# relay_module.net
KiCad netlist of a schematic drawn in EAGLE
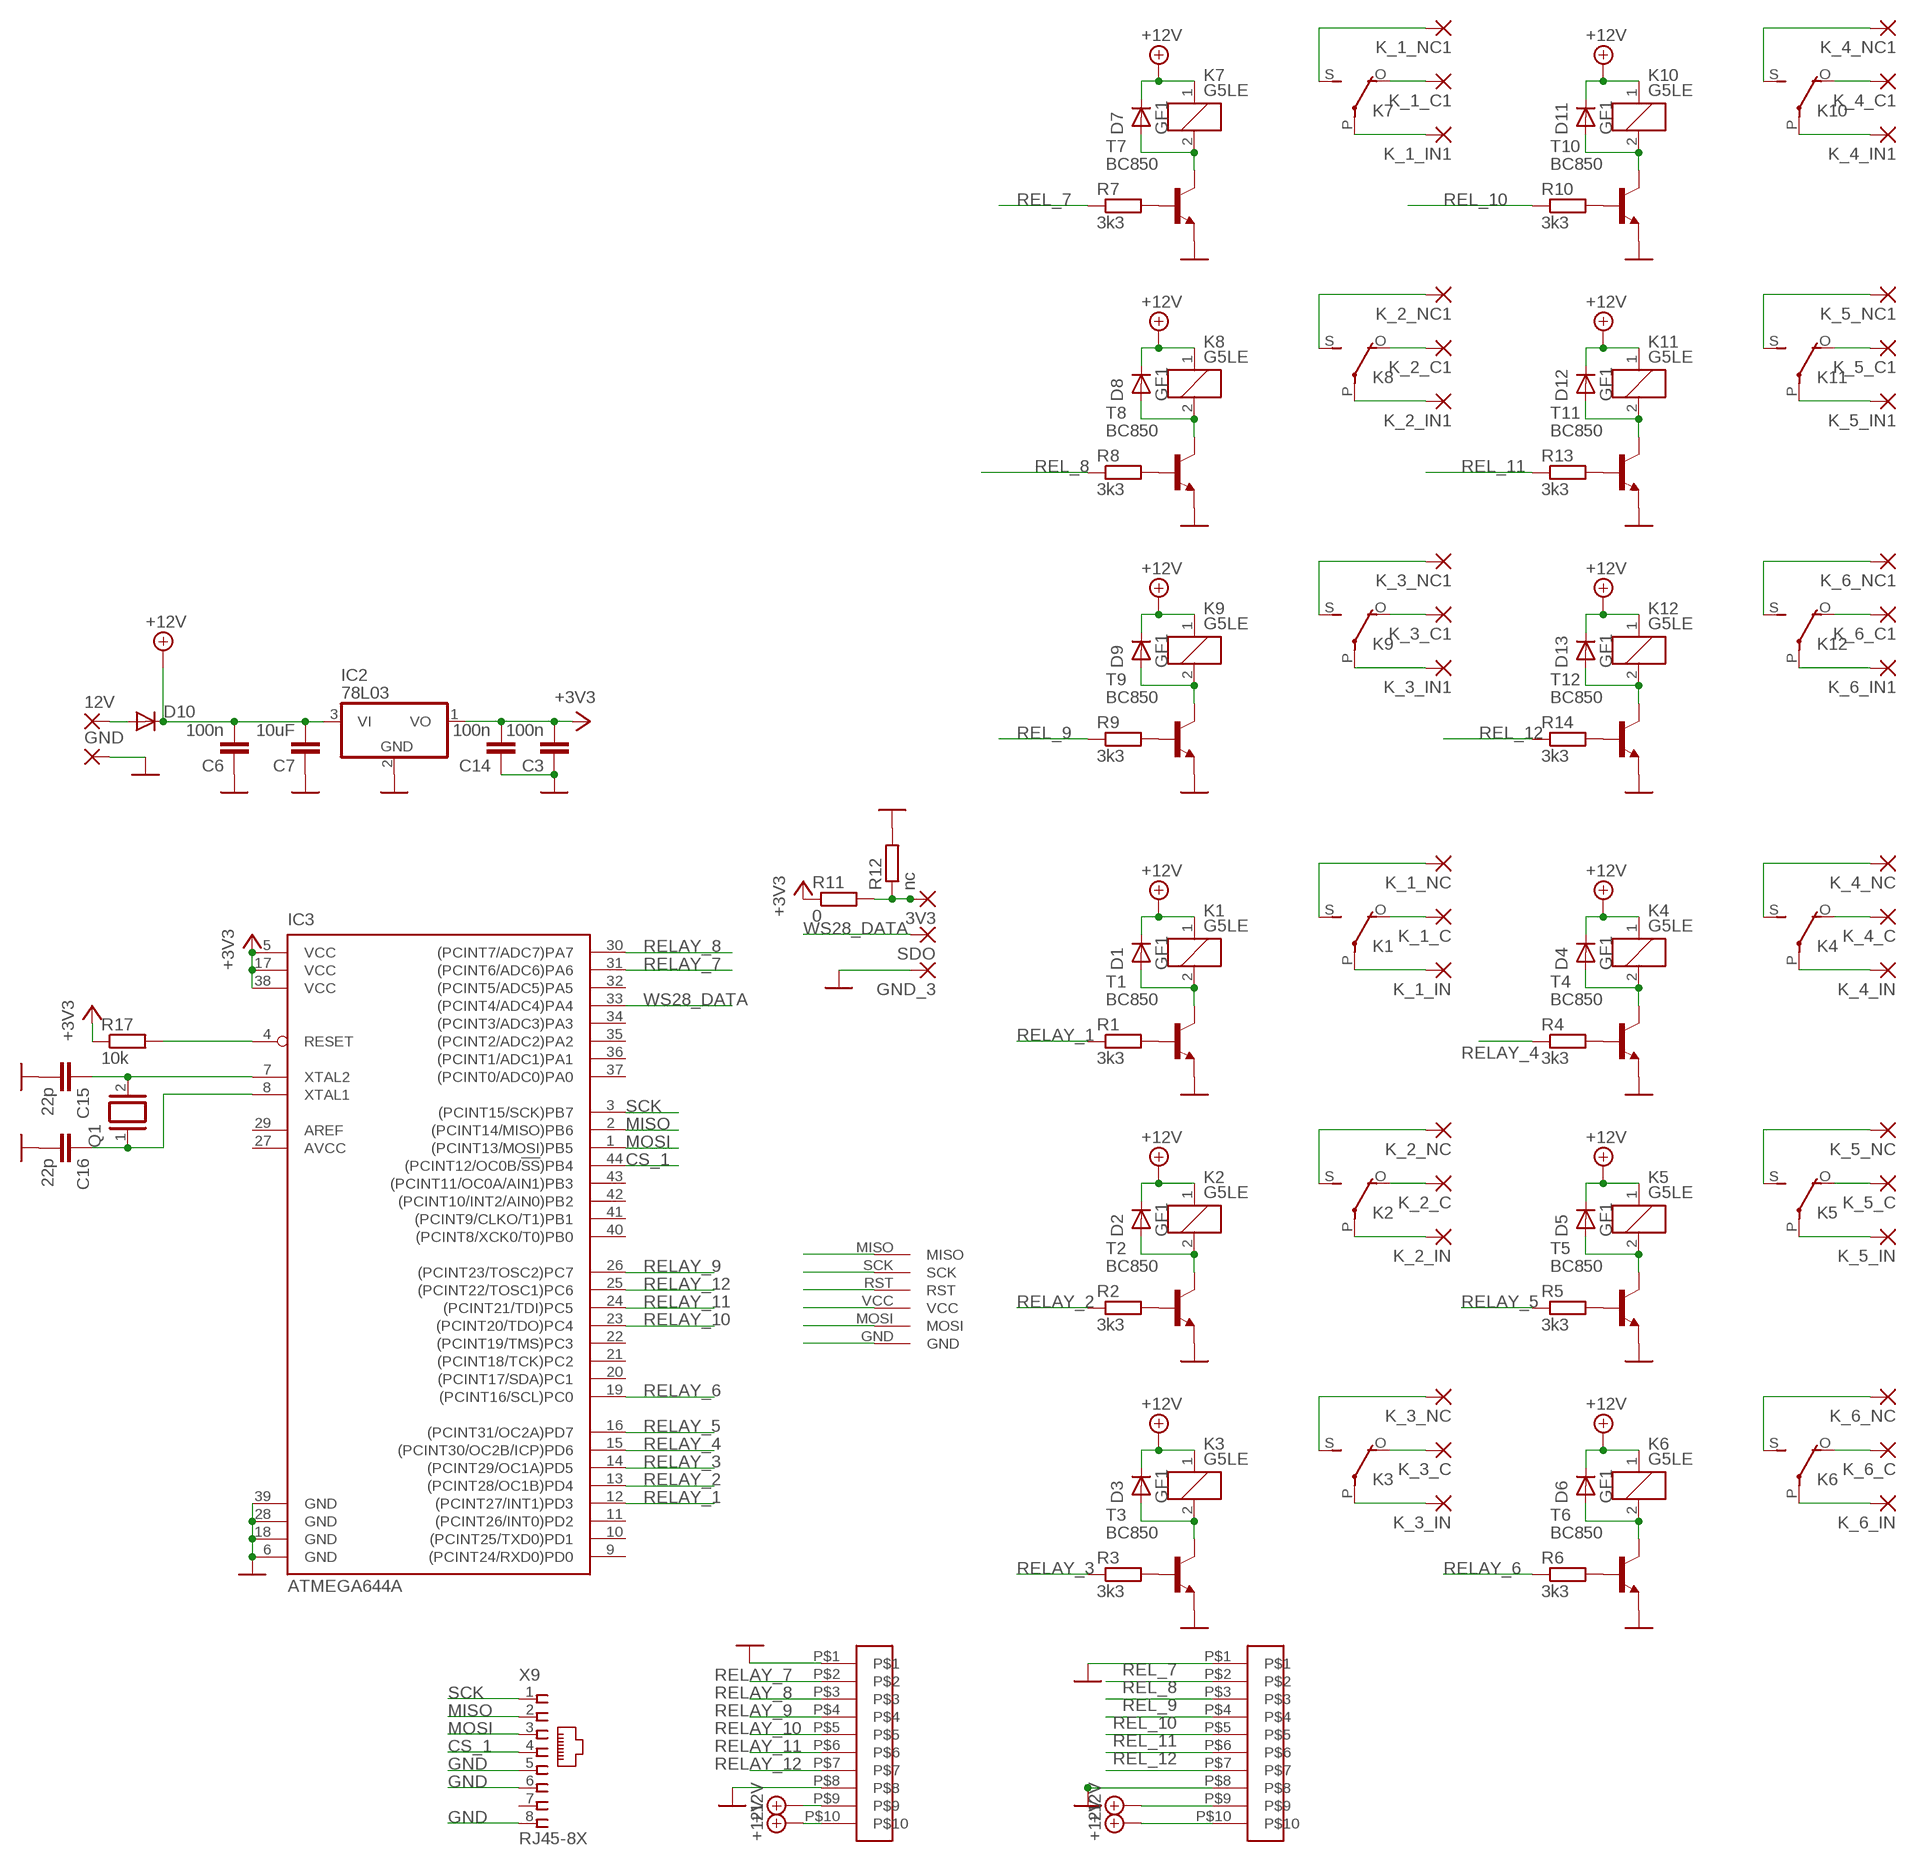
[diagram p0: schematic, sheet 1]

(export (version "E")
  (design (tool "Eeschema 10.0.6"))
  (components
    (comp (ref "3V3")
      (value "2,15/1,0")
      (footprint "eagle-import:2,15_1,0")
      (libsource (lib "eagle-import") (part "2,15/1,0"))
    )
    (comp (ref "12V")
      (value "2,54/0,8")
      (footprint "eagle-import:2,54_0,8")
      (libsource (lib "eagle-import") (part "2,54/0,8"))
    )
    (comp (ref "C3")
      (value "100n")
      (footprint "eagle-import:C1206")
      (libsource (lib "eagle-import") (part "C-EUC1206"))
    )
    (comp (ref "C6")
      (value "100n")
      (footprint "eagle-import:C1206")
      (libsource (lib "eagle-import") (part "C-EUC1206"))
    )
    (comp (ref "C7")
      (value "10uF")
      (footprint "eagle-import:C1206")
      (libsource (lib "eagle-import") (part "C-EUC1206"))
    )
    (comp (ref "C14")
      (value "100n")
      (footprint "eagle-import:C1206")
      (libsource (lib "eagle-import") (part "C-EUC1206"))
    )
    (comp (ref "C15")
      (value "22p")
      (footprint "eagle-import:C1206")
      (libsource (lib "eagle-import") (part "C-EUC1206"))
    )
    (comp (ref "C16")
      (value "22p")
      (footprint "eagle-import:C1206")
      (libsource (lib "eagle-import") (part "C-EUC1206"))
    )
    (comp (ref "D1")
      (value "GF1")
      (footprint "eagle-import:SMA-DO214AC")
      (libsource (lib "eagle-import") (part "GF1"))
    )
    (comp (ref "D2")
      (value "GF1")
      (footprint "eagle-import:SMA-DO214AC")
      (libsource (lib "eagle-import") (part "GF1"))
    )
    (comp (ref "D3")
      (value "GF1")
      (footprint "eagle-import:SMA-DO214AC")
      (libsource (lib "eagle-import") (part "GF1"))
    )
    (comp (ref "D4")
      (value "GF1")
      (footprint "eagle-import:SMA-DO214AC")
      (libsource (lib "eagle-import") (part "GF1"))
    )
    (comp (ref "D5")
      (value "GF1")
      (footprint "eagle-import:SMA-DO214AC")
      (libsource (lib "eagle-import") (part "GF1"))
    )
    (comp (ref "D6")
      (value "GF1")
      (footprint "eagle-import:SMA-DO214AC")
      (libsource (lib "eagle-import") (part "GF1"))
    )
    (comp (ref "D7")
      (value "GF1")
      (footprint "eagle-import:SMA-DO214AC")
      (libsource (lib "eagle-import") (part "GF1"))
    )
    (comp (ref "D8")
      (value "GF1")
      (footprint "eagle-import:SMA-DO214AC")
      (libsource (lib "eagle-import") (part "GF1"))
    )
    (comp (ref "D9")
      (value "GF1")
      (footprint "eagle-import:SMA-DO214AC")
      (libsource (lib "eagle-import") (part "GF1"))
    )
    (comp (ref "D10")
      (value "1N4148DO35-10")
      (footprint "eagle-import:DO35-10")
      (libsource (lib "eagle-import") (part "1N4148DO35-10"))
    )
    (comp (ref "D11")
      (value "GF1")
      (footprint "eagle-import:SMA-DO214AC")
      (libsource (lib "eagle-import") (part "GF1"))
    )
    (comp (ref "D12")
      (value "GF1")
      (footprint "eagle-import:SMA-DO214AC")
      (libsource (lib "eagle-import") (part "GF1"))
    )
    (comp (ref "D13")
      (value "GF1")
      (footprint "eagle-import:SMA-DO214AC")
      (libsource (lib "eagle-import") (part "GF1"))
    )
    (comp (ref "GND")
      (value "2,54/0,8")
      (footprint "eagle-import:2,54_0,8")
      (libsource (lib "eagle-import") (part "2,54/0,8"))
    )
    (comp (ref "GND_3")
      (value "2,15/1,0")
      (footprint "eagle-import:2,15_1,0")
      (libsource (lib "eagle-import") (part "2,15/1,0"))
    )
    (comp (ref "IC2")
      (value "78L03")
      (footprint "eagle-import:TO92")
      (libsource (lib "eagle-import") (part "78ZL05"))
    )
    (comp (ref "IC3")
      (value "ATMEGA644A")
      (footprint "eagle-import:TQFP44")
      (fields (field (name "MPN") "ATMEGA644PV-10AU"))
      (libsource (lib "eagle-import") (part "ATMEGA644A"))
    )
    (comp (ref "K1")
      (value "G5LE")
      (footprint "eagle-import:G5LE")
      (libsource (lib "eagle-import") (part "G5LE"))
    )
    (comp (ref "K2")
      (value "G5LE")
      (footprint "eagle-import:G5LE")
      (libsource (lib "eagle-import") (part "G5LE"))
    )
    (comp (ref "K3")
      (value "G5LE")
      (footprint "eagle-import:G5LE")
      (libsource (lib "eagle-import") (part "G5LE"))
    )
    (comp (ref "K4")
      (value "G5LE")
      (footprint "eagle-import:G5LE")
      (libsource (lib "eagle-import") (part "G5LE"))
    )
    (comp (ref "K5")
      (value "G5LE")
      (footprint "eagle-import:G5LE")
      (libsource (lib "eagle-import") (part "G5LE"))
    )
    (comp (ref "K6")
      (value "G5LE")
      (footprint "eagle-import:G5LE")
      (libsource (lib "eagle-import") (part "G5LE"))
    )
    (comp (ref "K7")
      (value "G5LE")
      (footprint "eagle-import:G5LE")
      (libsource (lib "eagle-import") (part "G5LE"))
    )
    (comp (ref "K8")
      (value "G5LE")
      (footprint "eagle-import:G5LE")
      (libsource (lib "eagle-import") (part "G5LE"))
    )
    (comp (ref "K9")
      (value "G5LE")
      (footprint "eagle-import:G5LE")
      (libsource (lib "eagle-import") (part "G5LE"))
    )
    (comp (ref "K10")
      (value "G5LE")
      (footprint "eagle-import:G5LE")
      (libsource (lib "eagle-import") (part "G5LE"))
    )
    (comp (ref "K11")
      (value "G5LE")
      (footprint "eagle-import:G5LE")
      (libsource (lib "eagle-import") (part "G5LE"))
    )
    (comp (ref "K12")
      (value "G5LE")
      (footprint "eagle-import:G5LE")
      (libsource (lib "eagle-import") (part "G5LE"))
    )
    (comp (ref "K_1_C")
      (value "2,54/0,8")
      (footprint "eagle-import:2,54_0,8")
      (libsource (lib "eagle-import") (part "2,54/0,8"))
    )
    (comp (ref "K_1_C1")
      (value "2,54/0,8")
      (footprint "eagle-import:2,54_0,8")
      (libsource (lib "eagle-import") (part "2,54/0,8"))
    )
    (comp (ref "K_1_IN")
      (value "2,54/0,8")
      (footprint "eagle-import:2,54_0,8")
      (libsource (lib "eagle-import") (part "2,54/0,8"))
    )
    (comp (ref "K_1_IN1")
      (value "2,54/0,8")
      (footprint "eagle-import:2,54_0,8")
      (libsource (lib "eagle-import") (part "2,54/0,8"))
    )
    (comp (ref "K_1_NC")
      (value "2,54/0,8")
      (footprint "eagle-import:2,54_0,8")
      (libsource (lib "eagle-import") (part "2,54/0,8"))
    )
    (comp (ref "K_1_NC1")
      (value "2,54/0,8")
      (footprint "eagle-import:2,54_0,8")
      (libsource (lib "eagle-import") (part "2,54/0,8"))
    )
    (comp (ref "K_2_C")
      (value "2,54/0,8")
      (footprint "eagle-import:2,54_0,8")
      (libsource (lib "eagle-import") (part "2,54/0,8"))
    )
    (comp (ref "K_2_C1")
      (value "2,54/0,8")
      (footprint "eagle-import:2,54_0,8")
      (libsource (lib "eagle-import") (part "2,54/0,8"))
    )
    (comp (ref "K_2_IN")
      (value "2,54/0,8")
      (footprint "eagle-import:2,54_0,8")
      (libsource (lib "eagle-import") (part "2,54/0,8"))
    )
    (comp (ref "K_2_IN1")
      (value "2,54/0,8")
      (footprint "eagle-import:2,54_0,8")
      (libsource (lib "eagle-import") (part "2,54/0,8"))
    )
    (comp (ref "K_2_NC")
      (value "2,54/0,8")
      (footprint "eagle-import:2,54_0,8")
      (libsource (lib "eagle-import") (part "2,54/0,8"))
    )
    (comp (ref "K_2_NC1")
      (value "2,54/0,8")
      (footprint "eagle-import:2,54_0,8")
      (libsource (lib "eagle-import") (part "2,54/0,8"))
    )
    (comp (ref "K_3_C")
      (value "2,54/0,8")
      (footprint "eagle-import:2,54_0,8")
      (libsource (lib "eagle-import") (part "2,54/0,8"))
    )
    (comp (ref "K_3_C1")
      (value "2,54/0,8")
      (footprint "eagle-import:2,54_0,8")
      (libsource (lib "eagle-import") (part "2,54/0,8"))
    )
    (comp (ref "K_3_IN")
      (value "2,54/0,8")
      (footprint "eagle-import:2,54_0,8")
      (libsource (lib "eagle-import") (part "2,54/0,8"))
    )
    (comp (ref "K_3_IN1")
      (value "2,54/0,8")
      (footprint "eagle-import:2,54_0,8")
      (libsource (lib "eagle-import") (part "2,54/0,8"))
    )
    (comp (ref "K_3_NC")
      (value "2,54/0,8")
      (footprint "eagle-import:2,54_0,8")
      (libsource (lib "eagle-import") (part "2,54/0,8"))
    )
    (comp (ref "K_3_NC1")
      (value "2,54/0,8")
      (footprint "eagle-import:2,54_0,8")
      (libsource (lib "eagle-import") (part "2,54/0,8"))
    )
    (comp (ref "K_4_C")
      (value "2,54/0,8")
      (footprint "eagle-import:2,54_0,8")
      (libsource (lib "eagle-import") (part "2,54/0,8"))
    )
    (comp (ref "K_4_C1")
      (value "2,54/0,8")
      (footprint "eagle-import:2,54_0,8")
      (libsource (lib "eagle-import") (part "2,54/0,8"))
    )
    (comp (ref "K_4_IN")
      (value "2,54/0,8")
      (footprint "eagle-import:2,54_0,8")
      (libsource (lib "eagle-import") (part "2,54/0,8"))
    )
    (comp (ref "K_4_IN1")
      (value "2,54/0,8")
      (footprint "eagle-import:2,54_0,8")
      (libsource (lib "eagle-import") (part "2,54/0,8"))
    )
    (comp (ref "K_4_NC")
      (value "2,54/0,8")
      (footprint "eagle-import:2,54_0,8")
      (libsource (lib "eagle-import") (part "2,54/0,8"))
    )
    (comp (ref "K_4_NC1")
      (value "2,54/0,8")
      (footprint "eagle-import:2,54_0,8")
      (libsource (lib "eagle-import") (part "2,54/0,8"))
    )
    (comp (ref "K_5_C")
      (value "2,54/0,8")
      (footprint "eagle-import:2,54_0,8")
      (libsource (lib "eagle-import") (part "2,54/0,8"))
    )
    (comp (ref "K_5_C1")
      (value "2,54/0,8")
      (footprint "eagle-import:2,54_0,8")
      (libsource (lib "eagle-import") (part "2,54/0,8"))
    )
    (comp (ref "K_5_IN")
      (value "2,54/0,8")
      (footprint "eagle-import:2,54_0,8")
      (libsource (lib "eagle-import") (part "2,54/0,8"))
    )
    (comp (ref "K_5_IN1")
      (value "2,54/0,8")
      (footprint "eagle-import:2,54_0,8")
      (libsource (lib "eagle-import") (part "2,54/0,8"))
    )
    (comp (ref "K_5_NC")
      (value "2,54/0,8")
      (footprint "eagle-import:2,54_0,8")
      (libsource (lib "eagle-import") (part "2,54/0,8"))
    )
    (comp (ref "K_5_NC1")
      (value "2,54/0,8")
      (footprint "eagle-import:2,54_0,8")
      (libsource (lib "eagle-import") (part "2,54/0,8"))
    )
    (comp (ref "K_6_C")
      (value "2,54/0,8")
      (footprint "eagle-import:2,54_0,8")
      (libsource (lib "eagle-import") (part "2,54/0,8"))
    )
    (comp (ref "K_6_C1")
      (value "2,54/0,8")
      (footprint "eagle-import:2,54_0,8")
      (libsource (lib "eagle-import") (part "2,54/0,8"))
    )
    (comp (ref "K_6_IN")
      (value "2,54/0,8")
      (footprint "eagle-import:2,54_0,8")
      (libsource (lib "eagle-import") (part "2,54/0,8"))
    )
    (comp (ref "K_6_IN1")
      (value "2,54/0,8")
      (footprint "eagle-import:2,54_0,8")
      (libsource (lib "eagle-import") (part "2,54/0,8"))
    )
    (comp (ref "K_6_NC")
      (value "2,54/0,8")
      (footprint "eagle-import:2,54_0,8")
      (libsource (lib "eagle-import") (part "2,54/0,8"))
    )
    (comp (ref "K_6_NC1")
      (value "2,54/0,8")
      (footprint "eagle-import:2,54_0,8")
      (libsource (lib "eagle-import") (part "2,54/0,8"))
    )
    (comp (ref "Q1")
      (value "XTAL/S")
      (footprint "eagle-import:QS")
      (libsource (lib "eagle-import") (part "XTAL/S"))
    )
    (comp (ref "R1")
      (value "3k3")
      (footprint "eagle-import:M3216")
      (libsource (lib "eagle-import") (part "R-EU_M3216"))
    )
    (comp (ref "R2")
      (value "3k3")
      (footprint "eagle-import:M3216")
      (libsource (lib "eagle-import") (part "R-EU_M3216"))
    )
    (comp (ref "R3")
      (value "3k3")
      (footprint "eagle-import:M3216")
      (libsource (lib "eagle-import") (part "R-EU_M3216"))
    )
    (comp (ref "R4")
      (value "3k3")
      (footprint "eagle-import:M3216")
      (libsource (lib "eagle-import") (part "R-EU_M3216"))
    )
    (comp (ref "R5")
      (value "3k3")
      (footprint "eagle-import:M3216")
      (libsource (lib "eagle-import") (part "R-EU_M3216"))
    )
    (comp (ref "R6")
      (value "3k3")
      (footprint "eagle-import:M3216")
      (libsource (lib "eagle-import") (part "R-EU_M3216"))
    )
    (comp (ref "R7")
      (value "3k3")
      (footprint "eagle-import:M3216")
      (libsource (lib "eagle-import") (part "R-EU_M3216"))
    )
    (comp (ref "R8")
      (value "3k3")
      (footprint "eagle-import:M3216")
      (libsource (lib "eagle-import") (part "R-EU_M3216"))
    )
    (comp (ref "R9")
      (value "3k3")
      (footprint "eagle-import:M3216")
      (libsource (lib "eagle-import") (part "R-EU_M3216"))
    )
    (comp (ref "R10")
      (value "3k3")
      (footprint "eagle-import:M3216")
      (libsource (lib "eagle-import") (part "R-EU_M3216"))
    )
    (comp (ref "R11")
      (value "0")
      (footprint "eagle-import:M3216")
      (libsource (lib "eagle-import") (part "R-EU_M3216"))
    )
    (comp (ref "R12")
      (value "nc")
      (footprint "eagle-import:M3216")
      (libsource (lib "eagle-import") (part "R-EU_M3216"))
    )
    (comp (ref "R13")
      (value "3k3")
      (footprint "eagle-import:M3216")
      (libsource (lib "eagle-import") (part "R-EU_M3216"))
    )
    (comp (ref "R14")
      (value "3k3")
      (footprint "eagle-import:M3216")
      (libsource (lib "eagle-import") (part "R-EU_M3216"))
    )
    (comp (ref "R17")
      (value "10k")
      (footprint "eagle-import:M3216")
      (libsource (lib "eagle-import") (part "R-EU_M3216"))
    )
    (comp (ref "SDO")
      (value "2,15/1,0")
      (footprint "eagle-import:2,15_1,0")
      (libsource (lib "eagle-import") (part "2,15/1,0"))
    )
    (comp (ref "T1")
      (value "BC850")
      (footprint "eagle-import:SOT23")
      (libsource (lib "eagle-import") (part "BC850"))
    )
    (comp (ref "T2")
      (value "BC850")
      (footprint "eagle-import:SOT23")
      (libsource (lib "eagle-import") (part "BC850"))
    )
    (comp (ref "T3")
      (value "BC850")
      (footprint "eagle-import:SOT23")
      (libsource (lib "eagle-import") (part "BC850"))
    )
    (comp (ref "T4")
      (value "BC850")
      (footprint "eagle-import:SOT23")
      (libsource (lib "eagle-import") (part "BC850"))
    )
    (comp (ref "T5")
      (value "BC850")
      (footprint "eagle-import:SOT23")
      (libsource (lib "eagle-import") (part "BC850"))
    )
    (comp (ref "T6")
      (value "BC850")
      (footprint "eagle-import:SOT23")
      (libsource (lib "eagle-import") (part "BC850"))
    )
    (comp (ref "T7")
      (value "BC850")
      (footprint "eagle-import:SOT23")
      (libsource (lib "eagle-import") (part "BC850"))
    )
    (comp (ref "T8")
      (value "BC850")
      (footprint "eagle-import:SOT23")
      (libsource (lib "eagle-import") (part "BC850"))
    )
    (comp (ref "T9")
      (value "BC850")
      (footprint "eagle-import:SOT23")
      (libsource (lib "eagle-import") (part "BC850"))
    )
    (comp (ref "T10")
      (value "BC850")
      (footprint "eagle-import:SOT23")
      (libsource (lib "eagle-import") (part "BC850"))
    )
    (comp (ref "T11")
      (value "BC850")
      (footprint "eagle-import:SOT23")
      (libsource (lib "eagle-import") (part "BC850"))
    )
    (comp (ref "T12")
      (value "BC850")
      (footprint "eagle-import:SOT23")
      (libsource (lib "eagle-import") (part "BC850"))
    )
    (comp (ref "U$1")
      (value "10P")
      (footprint "eagle-import:10P")
      (libsource (lib "eagle-import") (part "10P"))
    )
    (comp (ref "U$2")
      (value "AVR_ISP")
      (footprint "eagle-import:AVR_ISP")
      (libsource (lib "eagle-import") (part "AVR_ISP"))
    )
    (comp (ref "U$3")
      (value "10P")
      (footprint "eagle-import:10P")
      (libsource (lib "eagle-import") (part "10P"))
    )
    (comp (ref "X9")
      (value "RJ45-8X")
      (footprint "eagle-import:RJ45-NO-SHIELD")
      (libsource (lib "eagle-import") (part "RJ45-8X"))
    )
  )
  (nets
    (net (code "1") (name "+3V3") (class "Default")
      (node (ref "C14") (pin "2") (pinfunction "2_2") (pintype "passive"))
      (node (ref "C3") (pin "2") (pinfunction "2_2") (pintype "passive"))
      (node (ref "IC2") (pin "1") (pinfunction "VO_1") (pintype "passive"))
      (node (ref "IC3") (pin "17") (pinfunction "VCC_17") (pintype "power_in"))
      (node (ref "IC3") (pin "38") (pinfunction "VCC_38") (pintype "power_in"))
      (node (ref "IC3") (pin "5") (pinfunction "VCC_5") (pintype "power_in"))
      (node (ref "R11") (pin "1") (pinfunction "1_1") (pintype "passive"))
      (node (ref "R17") (pin "1") (pinfunction "1_1") (pintype "passive"))
      (node (ref "U$2") (pin "VCC") (pinfunction "VCC_VCC") (pintype "bidirectional"))
    )
    (net (code "2") (name "+12V") (class "Default")
      (node (ref "C6") (pin "2") (pinfunction "2_2") (pintype "passive"))
      (node (ref "C7") (pin "2") (pinfunction "2_2") (pintype "passive"))
      (node (ref "D1") (pin "K") (pinfunction "C_K") (pintype "passive"))
      (node (ref "D10") (pin "C") (pinfunction "C_C") (pintype "passive"))
      (node (ref "D11") (pin "K") (pinfunction "C_K") (pintype "passive"))
      (node (ref "D12") (pin "K") (pinfunction "C_K") (pintype "passive"))
      (node (ref "D13") (pin "K") (pinfunction "C_K") (pintype "passive"))
      (node (ref "D2") (pin "K") (pinfunction "C_K") (pintype "passive"))
      (node (ref "D3") (pin "K") (pinfunction "C_K") (pintype "passive"))
      (node (ref "D4") (pin "K") (pinfunction "C_K") (pintype "passive"))
      (node (ref "D5") (pin "K") (pinfunction "C_K") (pintype "passive"))
      (node (ref "D6") (pin "K") (pinfunction "C_K") (pintype "passive"))
      (node (ref "D7") (pin "K") (pinfunction "C_K") (pintype "passive"))
      (node (ref "D8") (pin "K") (pinfunction "C_K") (pintype "passive"))
      (node (ref "D9") (pin "K") (pinfunction "C_K") (pintype "passive"))
      (node (ref "IC2") (pin "3") (pinfunction "VI_3") (pintype "input"))
      (node (ref "K1") (pin "1") (pinfunction "1_1") (pintype "passive"))
      (node (ref "K10") (pin "1") (pinfunction "1_1") (pintype "passive"))
      (node (ref "K11") (pin "1") (pinfunction "1_1") (pintype "passive"))
      (node (ref "K12") (pin "1") (pinfunction "1_1") (pintype "passive"))
      (node (ref "K2") (pin "1") (pinfunction "1_1") (pintype "passive"))
      (node (ref "K3") (pin "1") (pinfunction "1_1") (pintype "passive"))
      (node (ref "K4") (pin "1") (pinfunction "1_1") (pintype "passive"))
      (node (ref "K5") (pin "1") (pinfunction "1_1") (pintype "passive"))
      (node (ref "K6") (pin "1") (pinfunction "1_1") (pintype "passive"))
      (node (ref "K7") (pin "1") (pinfunction "1_1") (pintype "passive"))
      (node (ref "K8") (pin "1") (pinfunction "1_1") (pintype "passive"))
      (node (ref "K9") (pin "1") (pinfunction "1_1") (pintype "passive"))
      (node (ref "U$1") (pin "P$10") (pinfunction "P$10_P$10") (pintype "bidirectional"))
      (node (ref "U$1") (pin "P$9") (pinfunction "P$9_P$9") (pintype "bidirectional"))
      (node (ref "U$3") (pin "P$10") (pinfunction "P$10_P$10") (pintype "bidirectional"))
      (node (ref "U$3") (pin "P$9") (pinfunction "P$9_P$9") (pintype "bidirectional"))
    )
    (net (code "3") (name "/AVCC") (class "Default")
      (node (ref "IC3") (pin "27") (pinfunction "AVCC_27") (pintype "power_in"))
    )
    (net (code "4") (name "/CS_1") (class "Default")
      (node (ref "IC3") (pin "44") (pinfunction "(PCINT12/OC0B/~{SS})PB4_44") (pintype "bidirectional"))
      (node (ref "X9") (pin "4") (pinfunction "4_4") (pintype "passive"))
    )
    (net (code "5") (name "/MISO") (class "Default")
      (node (ref "IC3") (pin "2") (pinfunction "(PCINT14/MISO)PB6_2") (pintype "bidirectional"))
      (node (ref "U$2") (pin "MISO") (pinfunction "MISO_MISO") (pintype "bidirectional"))
      (node (ref "X9") (pin "2") (pinfunction "2_2") (pintype "passive"))
    )
    (net (code "6") (name "/MOSI") (class "Default")
      (node (ref "IC3") (pin "1") (pinfunction "(PCINT13/MOSI)PB5_1") (pintype "bidirectional"))
      (node (ref "U$2") (pin "MOSI") (pinfunction "MOSI_MOSI") (pintype "bidirectional"))
      (node (ref "X9") (pin "3") (pinfunction "3_3") (pintype "passive"))
    )
    (net (code "7") (name "/RELAY_1") (class "Default")
      (node (ref "IC3") (pin "12") (pinfunction "(PCINT27/INT1)PD3_12") (pintype "bidirectional"))
      (node (ref "R1") (pin "1") (pinfunction "1_1") (pintype "passive"))
    )
    (net (code "8") (name "/RELAY_2") (class "Default")
      (node (ref "IC3") (pin "13") (pinfunction "(PCINT28/OC1B)PD4_13") (pintype "bidirectional"))
      (node (ref "R2") (pin "1") (pinfunction "1_1") (pintype "passive"))
    )
    (net (code "9") (name "/RELAY_3") (class "Default")
      (node (ref "IC3") (pin "14") (pinfunction "(PCINT29/OC1A)PD5_14") (pintype "bidirectional"))
      (node (ref "R3") (pin "1") (pinfunction "1_1") (pintype "passive"))
    )
    (net (code "10") (name "/RELAY_4") (class "Default")
      (node (ref "IC3") (pin "15") (pinfunction "(PCINT30/OC2B/ICP)PD6_15") (pintype "bidirectional"))
      (node (ref "R4") (pin "1") (pinfunction "1_1") (pintype "passive"))
    )
    (net (code "11") (name "/RELAY_5") (class "Default")
      (node (ref "IC3") (pin "16") (pinfunction "(PCINT31/OC2A)PD7_16") (pintype "bidirectional"))
      (node (ref "R5") (pin "1") (pinfunction "1_1") (pintype "passive"))
    )
    (net (code "12") (name "/RELAY_6") (class "Default")
      (node (ref "IC3") (pin "19") (pinfunction "(PCINT16/SCL)PC0_19") (pintype "output"))
      (node (ref "R6") (pin "1") (pinfunction "1_1") (pintype "passive"))
    )
    (net (code "13") (name "/RELAY_7") (class "Default")
      (node (ref "IC3") (pin "31") (pinfunction "(PCINT6/ADC6)PA6_31") (pintype "bidirectional"))
      (node (ref "U$1") (pin "P$2") (pinfunction "P$2_P$2") (pintype "bidirectional"))
    )
    (net (code "14") (name "/RELAY_8") (class "Default")
      (node (ref "IC3") (pin "30") (pinfunction "(PCINT7/ADC7)PA7_30") (pintype "bidirectional"))
      (node (ref "U$1") (pin "P$3") (pinfunction "P$3_P$3") (pintype "bidirectional"))
    )
    (net (code "15") (name "/RELAY_9") (class "Default")
      (node (ref "IC3") (pin "26") (pinfunction "(PCINT23/TOSC2)PC7_26") (pintype "output"))
      (node (ref "U$1") (pin "P$4") (pinfunction "P$4_P$4") (pintype "bidirectional"))
    )
    (net (code "16") (name "/RELAY_10") (class "Default")
      (node (ref "IC3") (pin "23") (pinfunction "(PCINT20/TDO)PC4_23") (pintype "output"))
      (node (ref "U$1") (pin "P$5") (pinfunction "P$5_P$5") (pintype "bidirectional"))
    )
    (net (code "17") (name "/RELAY_11") (class "Default")
      (node (ref "IC3") (pin "24") (pinfunction "(PCINT21/TDI)PC5_24") (pintype "output"))
      (node (ref "U$1") (pin "P$6") (pinfunction "P$6_P$6") (pintype "bidirectional"))
    )
    (net (code "18") (name "/RELAY_12") (class "Default")
      (node (ref "IC3") (pin "25") (pinfunction "(PCINT22/TOSC1)PC6_25") (pintype "output"))
      (node (ref "U$1") (pin "P$7") (pinfunction "P$7_P$7") (pintype "bidirectional"))
    )
    (net (code "19") (name "/REL_7") (class "Default")
      (node (ref "R7") (pin "1") (pinfunction "1_1") (pintype "passive"))
      (node (ref "U$3") (pin "P$2") (pinfunction "P$2_P$2") (pintype "bidirectional"))
    )
    (net (code "20") (name "/REL_8") (class "Default")
      (node (ref "R8") (pin "1") (pinfunction "1_1") (pintype "passive"))
      (node (ref "U$3") (pin "P$3") (pinfunction "P$3_P$3") (pintype "bidirectional"))
    )
    (net (code "21") (name "/REL_9") (class "Default")
      (node (ref "R9") (pin "1") (pinfunction "1_1") (pintype "passive"))
      (node (ref "U$3") (pin "P$4") (pinfunction "P$4_P$4") (pintype "bidirectional"))
    )
    (net (code "22") (name "/REL_10") (class "Default")
      (node (ref "R10") (pin "1") (pinfunction "1_1") (pintype "passive"))
      (node (ref "U$3") (pin "P$5") (pinfunction "P$5_P$5") (pintype "bidirectional"))
    )
    (net (code "23") (name "/REL_11") (class "Default")
      (node (ref "R13") (pin "1") (pinfunction "1_1") (pintype "passive"))
      (node (ref "U$3") (pin "P$6") (pinfunction "P$6_P$6") (pintype "bidirectional"))
    )
    (net (code "24") (name "/REL_12") (class "Default")
      (node (ref "R14") (pin "1") (pinfunction "1_1") (pintype "passive"))
      (node (ref "U$3") (pin "P$7") (pinfunction "P$7_P$7") (pintype "bidirectional"))
    )
    (net (code "25") (name "/RESET") (class "Default")
      (node (ref "IC3") (pin "4") (pinfunction "RESET_4") (pintype "input"))
      (node (ref "R17") (pin "2") (pinfunction "2_2") (pintype "passive"))
      (node (ref "U$2") (pin "RST") (pinfunction "RST_RST") (pintype "bidirectional"))
    )
    (net (code "26") (name "/SCK") (class "Default")
      (node (ref "IC3") (pin "3") (pinfunction "(PCINT15/SCK)PB7_3") (pintype "bidirectional"))
      (node (ref "U$2") (pin "SCK") (pinfunction "SCK_SCK") (pintype "bidirectional"))
      (node (ref "X9") (pin "1") (pinfunction "1_1") (pintype "passive"))
    )
    (net (code "27") (name "/WS28_DATA") (class "Default")
      (node (ref "IC3") (pin "33") (pinfunction "(PCINT4/ADC4)PA4_33") (pintype "bidirectional"))
      (node (ref "SDO") (pin "1") (pinfunction "P_1") (pintype "passive"))
    )
    (net (code "28") (name "GND") (class "Default")
      (node (ref "C14") (pin "1") (pinfunction "1_1") (pintype "passive"))
      (node (ref "C15") (pin "2") (pinfunction "2_2") (pintype "passive"))
      (node (ref "C16") (pin "2") (pinfunction "2_2") (pintype "passive"))
      (node (ref "C3") (pin "1") (pinfunction "1_1") (pintype "passive"))
      (node (ref "C6") (pin "1") (pinfunction "1_1") (pintype "passive"))
      (node (ref "C7") (pin "1") (pinfunction "1_1") (pintype "passive"))
      (node (ref "GND") (pin "1") (pinfunction "P_1") (pintype "passive"))
      (node (ref "GND_3") (pin "1") (pinfunction "P_1") (pintype "passive"))
      (node (ref "IC2") (pin "2") (pinfunction "GND_2") (pintype "passive"))
      (node (ref "IC3") (pin "18") (pinfunction "GND_18") (pintype "power_in"))
      (node (ref "IC3") (pin "28") (pinfunction "GND_28") (pintype "power_in"))
      (node (ref "IC3") (pin "39") (pinfunction "GND_39") (pintype "power_in"))
      (node (ref "IC3") (pin "6") (pinfunction "GND_6") (pintype "power_in"))
      (node (ref "R12") (pin "2") (pinfunction "2_2") (pintype "passive"))
      (node (ref "T1") (pin "2") (pinfunction "E_2") (pintype "passive"))
      (node (ref "T10") (pin "2") (pinfunction "E_2") (pintype "passive"))
      (node (ref "T11") (pin "2") (pinfunction "E_2") (pintype "passive"))
      (node (ref "T12") (pin "2") (pinfunction "E_2") (pintype "passive"))
      (node (ref "T2") (pin "2") (pinfunction "E_2") (pintype "passive"))
      (node (ref "T3") (pin "2") (pinfunction "E_2") (pintype "passive"))
      (node (ref "T4") (pin "2") (pinfunction "E_2") (pintype "passive"))
      (node (ref "T5") (pin "2") (pinfunction "E_2") (pintype "passive"))
      (node (ref "T6") (pin "2") (pinfunction "E_2") (pintype "passive"))
      (node (ref "T7") (pin "2") (pinfunction "E_2") (pintype "passive"))
      (node (ref "T8") (pin "2") (pinfunction "E_2") (pintype "passive"))
      (node (ref "T9") (pin "2") (pinfunction "E_2") (pintype "passive"))
      (node (ref "U$1") (pin "P$1") (pinfunction "P$1_P$1") (pintype "bidirectional"))
      (node (ref "U$1") (pin "P$8") (pinfunction "P$8_P$8") (pintype "bidirectional"))
      (node (ref "U$2") (pin "GND") (pinfunction "GND_GND") (pintype "bidirectional"))
      (node (ref "U$3") (pin "P$1") (pinfunction "P$1_P$1") (pintype "bidirectional"))
      (node (ref "U$3") (pin "P$8") (pinfunction "P$8_P$8") (pintype "bidirectional"))
      (node (ref "X9") (pin "5") (pinfunction "5_5") (pintype "passive"))
      (node (ref "X9") (pin "6") (pinfunction "6_6") (pintype "passive"))
      (node (ref "X9") (pin "8") (pinfunction "8_8") (pintype "passive"))
    )
    (net (code "29") (name "Net-(3V3-P)") (class "Default")
      (node (ref "3V3") (pin "1") (pinfunction "P_1") (pintype "passive"))
      (node (ref "R11") (pin "2") (pinfunction "2_2") (pintype "passive"))
      (node (ref "R12") (pin "1") (pinfunction "1_1") (pintype "passive"))
    )
    (net (code "30") (name "Net-(12V-P)") (class "Default")
      (node (ref "12V") (pin "1") (pinfunction "P_1") (pintype "passive"))
      (node (ref "D10") (pin "A") (pinfunction "A_A") (pintype "passive"))
    )
    (net (code "31") (name "Net-(IC3-XTAL1)") (class "Default")
      (node (ref "C16") (pin "1") (pinfunction "1_1") (pintype "passive"))
      (node (ref "IC3") (pin "8") (pinfunction "XTAL1_8") (pintype "bidirectional"))
      (node (ref "Q1") (pin "1") (pinfunction "1_1") (pintype "passive"))
    )
    (net (code "32") (name "Net-(IC3-XTAL2)") (class "Default")
      (node (ref "C15") (pin "1") (pinfunction "1_1") (pintype "passive"))
      (node (ref "IC3") (pin "7") (pinfunction "XTAL2_7") (pintype "bidirectional"))
      (node (ref "Q1") (pin "2") (pinfunction "2_2") (pintype "passive"))
    )
    (net (code "33") (name "Net-(K_1_C-P)") (class "Default")
      (node (ref "K1") (pin "O") (pinfunction "O_O") (pintype "passive"))
      (node (ref "K_1_C") (pin "1") (pinfunction "P_1") (pintype "passive"))
    )
    (net (code "34") (name "Net-(K_1_C1-P)") (class "Default")
      (node (ref "K7") (pin "O") (pinfunction "O_O") (pintype "passive"))
      (node (ref "K_1_C1") (pin "1") (pinfunction "P_1") (pintype "passive"))
    )
    (net (code "35") (name "Net-(K_1_IN-P)") (class "Default")
      (node (ref "K1") (pin "P") (pinfunction "P_P") (pintype "passive"))
      (node (ref "K_1_IN") (pin "1") (pinfunction "P_1") (pintype "passive"))
    )
    (net (code "36") (name "Net-(K_1_IN1-P)") (class "Default")
      (node (ref "K7") (pin "P") (pinfunction "P_P") (pintype "passive"))
      (node (ref "K_1_IN1") (pin "1") (pinfunction "P_1") (pintype "passive"))
    )
    (net (code "37") (name "Net-(K_1_NC-P)") (class "Default")
      (node (ref "K1") (pin "S") (pinfunction "S_S") (pintype "passive"))
      (node (ref "K_1_NC") (pin "1") (pinfunction "P_1") (pintype "passive"))
    )
    (net (code "38") (name "Net-(K_1_NC1-P)") (class "Default")
      (node (ref "K7") (pin "S") (pinfunction "S_S") (pintype "passive"))
      (node (ref "K_1_NC1") (pin "1") (pinfunction "P_1") (pintype "passive"))
    )
    (net (code "39") (name "Net-(K_2_C-P)") (class "Default")
      (node (ref "K2") (pin "O") (pinfunction "O_O") (pintype "passive"))
      (node (ref "K_2_C") (pin "1") (pinfunction "P_1") (pintype "passive"))
    )
    (net (code "40") (name "Net-(K_2_C1-P)") (class "Default")
      (node (ref "K8") (pin "O") (pinfunction "O_O") (pintype "passive"))
      (node (ref "K_2_C1") (pin "1") (pinfunction "P_1") (pintype "passive"))
    )
    (net (code "41") (name "Net-(K_2_IN-P)") (class "Default")
      (node (ref "K2") (pin "P") (pinfunction "P_P") (pintype "passive"))
      (node (ref "K_2_IN") (pin "1") (pinfunction "P_1") (pintype "passive"))
    )
    (net (code "42") (name "Net-(K_2_IN1-P)") (class "Default")
      (node (ref "K8") (pin "P") (pinfunction "P_P") (pintype "passive"))
      (node (ref "K_2_IN1") (pin "1") (pinfunction "P_1") (pintype "passive"))
    )
    (net (code "43") (name "Net-(K_2_NC-P)") (class "Default")
      (node (ref "K2") (pin "S") (pinfunction "S_S") (pintype "passive"))
      (node (ref "K_2_NC") (pin "1") (pinfunction "P_1") (pintype "passive"))
    )
    (net (code "44") (name "Net-(K_2_NC1-P)") (class "Default")
      (node (ref "K8") (pin "S") (pinfunction "S_S") (pintype "passive"))
      (node (ref "K_2_NC1") (pin "1") (pinfunction "P_1") (pintype "passive"))
    )
    (net (code "45") (name "Net-(K_3_C-P)") (class "Default")
      (node (ref "K3") (pin "O") (pinfunction "O_O") (pintype "passive"))
      (node (ref "K_3_C") (pin "1") (pinfunction "P_1") (pintype "passive"))
    )
    (net (code "46") (name "Net-(K_3_C1-P)") (class "Default")
      (node (ref "K9") (pin "O") (pinfunction "O_O") (pintype "passive"))
      (node (ref "K_3_C1") (pin "1") (pinfunction "P_1") (pintype "passive"))
    )
    (net (code "47") (name "Net-(K_3_IN-P)") (class "Default")
      (node (ref "K3") (pin "P") (pinfunction "P_P") (pintype "passive"))
      (node (ref "K_3_IN") (pin "1") (pinfunction "P_1") (pintype "passive"))
    )
    (net (code "48") (name "Net-(K_3_IN1-P)") (class "Default")
      (node (ref "K9") (pin "P") (pinfunction "P_P") (pintype "passive"))
      (node (ref "K_3_IN1") (pin "1") (pinfunction "P_1") (pintype "passive"))
    )
    (net (code "49") (name "Net-(K_3_NC-P)") (class "Default")
      (node (ref "K3") (pin "S") (pinfunction "S_S") (pintype "passive"))
      (node (ref "K_3_NC") (pin "1") (pinfunction "P_1") (pintype "passive"))
    )
    (net (code "50") (name "Net-(K_3_NC1-P)") (class "Default")
      (node (ref "K9") (pin "S") (pinfunction "S_S") (pintype "passive"))
      (node (ref "K_3_NC1") (pin "1") (pinfunction "P_1") (pintype "passive"))
    )
    (net (code "51") (name "Net-(K_4_C-P)") (class "Default")
      (node (ref "K4") (pin "O") (pinfunction "O_O") (pintype "passive"))
      (node (ref "K_4_C") (pin "1") (pinfunction "P_1") (pintype "passive"))
    )
    (net (code "52") (name "Net-(K_4_C1-P)") (class "Default")
      (node (ref "K10") (pin "O") (pinfunction "O_O") (pintype "passive"))
      (node (ref "K_4_C1") (pin "1") (pinfunction "P_1") (pintype "passive"))
    )
    (net (code "53") (name "Net-(K_4_IN-P)") (class "Default")
      (node (ref "K4") (pin "P") (pinfunction "P_P") (pintype "passive"))
      (node (ref "K_4_IN") (pin "1") (pinfunction "P_1") (pintype "passive"))
    )
    (net (code "54") (name "Net-(K_4_IN1-P)") (class "Default")
      (node (ref "K10") (pin "P") (pinfunction "P_P") (pintype "passive"))
      (node (ref "K_4_IN1") (pin "1") (pinfunction "P_1") (pintype "passive"))
    )
    (net (code "55") (name "Net-(K_4_NC-P)") (class "Default")
      (node (ref "K4") (pin "S") (pinfunction "S_S") (pintype "passive"))
      (node (ref "K_4_NC") (pin "1") (pinfunction "P_1") (pintype "passive"))
    )
    (net (code "56") (name "Net-(K_4_NC1-P)") (class "Default")
      (node (ref "K10") (pin "S") (pinfunction "S_S") (pintype "passive"))
      (node (ref "K_4_NC1") (pin "1") (pinfunction "P_1") (pintype "passive"))
    )
    (net (code "57") (name "Net-(K_5_C-P)") (class "Default")
      (node (ref "K5") (pin "O") (pinfunction "O_O") (pintype "passive"))
      (node (ref "K_5_C") (pin "1") (pinfunction "P_1") (pintype "passive"))
    )
    (net (code "58") (name "Net-(K_5_C1-P)") (class "Default")
      (node (ref "K11") (pin "O") (pinfunction "O_O") (pintype "passive"))
      (node (ref "K_5_C1") (pin "1") (pinfunction "P_1") (pintype "passive"))
    )
    (net (code "59") (name "Net-(K_5_IN-P)") (class "Default")
      (node (ref "K5") (pin "P") (pinfunction "P_P") (pintype "passive"))
      (node (ref "K_5_IN") (pin "1") (pinfunction "P_1") (pintype "passive"))
    )
    (net (code "60") (name "Net-(K_5_IN1-P)") (class "Default")
      (node (ref "K11") (pin "P") (pinfunction "P_P") (pintype "passive"))
      (node (ref "K_5_IN1") (pin "1") (pinfunction "P_1") (pintype "passive"))
    )
    (net (code "61") (name "Net-(K_5_NC-P)") (class "Default")
      (node (ref "K5") (pin "S") (pinfunction "S_S") (pintype "passive"))
      (node (ref "K_5_NC") (pin "1") (pinfunction "P_1") (pintype "passive"))
    )
    (net (code "62") (name "Net-(K_5_NC1-P)") (class "Default")
      (node (ref "K11") (pin "S") (pinfunction "S_S") (pintype "passive"))
      (node (ref "K_5_NC1") (pin "1") (pinfunction "P_1") (pintype "passive"))
    )
    (net (code "63") (name "Net-(K_6_C-P)") (class "Default")
      (node (ref "K6") (pin "O") (pinfunction "O_O") (pintype "passive"))
      (node (ref "K_6_C") (pin "1") (pinfunction "P_1") (pintype "passive"))
    )
    (net (code "64") (name "Net-(K_6_C1-P)") (class "Default")
      (node (ref "K12") (pin "O") (pinfunction "O_O") (pintype "passive"))
      (node (ref "K_6_C1") (pin "1") (pinfunction "P_1") (pintype "passive"))
    )
    (net (code "65") (name "Net-(K_6_IN-P)") (class "Default")
      (node (ref "K6") (pin "P") (pinfunction "P_P") (pintype "passive"))
      (node (ref "K_6_IN") (pin "1") (pinfunction "P_1") (pintype "passive"))
    )
    (net (code "66") (name "Net-(K_6_IN1-P)") (class "Default")
      (node (ref "K12") (pin "P") (pinfunction "P_P") (pintype "passive"))
      (node (ref "K_6_IN1") (pin "1") (pinfunction "P_1") (pintype "passive"))
    )
    (net (code "67") (name "Net-(K_6_NC-P)") (class "Default")
      (node (ref "K6") (pin "S") (pinfunction "S_S") (pintype "passive"))
      (node (ref "K_6_NC") (pin "1") (pinfunction "P_1") (pintype "passive"))
    )
    (net (code "68") (name "Net-(K_6_NC1-P)") (class "Default")
      (node (ref "K12") (pin "S") (pinfunction "S_S") (pintype "passive"))
      (node (ref "K_6_NC1") (pin "1") (pinfunction "P_1") (pintype "passive"))
    )
    (net (code "69") (name "Net-(T1-B)") (class "Default")
      (node (ref "R1") (pin "2") (pinfunction "2_2") (pintype "passive"))
      (node (ref "T1") (pin "1") (pinfunction "B_1") (pintype "passive"))
    )
    (net (code "70") (name "Net-(T1-C)") (class "Default")
      (node (ref "D1") (pin "A") (pinfunction "A_A") (pintype "passive"))
      (node (ref "K1") (pin "2") (pinfunction "2_2") (pintype "passive"))
      (node (ref "T1") (pin "3") (pinfunction "C_3") (pintype "passive"))
    )
    (net (code "71") (name "Net-(T2-B)") (class "Default")
      (node (ref "R2") (pin "2") (pinfunction "2_2") (pintype "passive"))
      (node (ref "T2") (pin "1") (pinfunction "B_1") (pintype "passive"))
    )
    (net (code "72") (name "Net-(T2-C)") (class "Default")
      (node (ref "D2") (pin "A") (pinfunction "A_A") (pintype "passive"))
      (node (ref "K2") (pin "2") (pinfunction "2_2") (pintype "passive"))
      (node (ref "T2") (pin "3") (pinfunction "C_3") (pintype "passive"))
    )
    (net (code "73") (name "Net-(T3-B)") (class "Default")
      (node (ref "R3") (pin "2") (pinfunction "2_2") (pintype "passive"))
      (node (ref "T3") (pin "1") (pinfunction "B_1") (pintype "passive"))
    )
    (net (code "74") (name "Net-(T3-C)") (class "Default")
      (node (ref "D3") (pin "A") (pinfunction "A_A") (pintype "passive"))
      (node (ref "K3") (pin "2") (pinfunction "2_2") (pintype "passive"))
      (node (ref "T3") (pin "3") (pinfunction "C_3") (pintype "passive"))
    )
    (net (code "75") (name "Net-(T4-B)") (class "Default")
      (node (ref "R4") (pin "2") (pinfunction "2_2") (pintype "passive"))
      (node (ref "T4") (pin "1") (pinfunction "B_1") (pintype "passive"))
    )
    (net (code "76") (name "Net-(T4-C)") (class "Default")
      (node (ref "D4") (pin "A") (pinfunction "A_A") (pintype "passive"))
      (node (ref "K4") (pin "2") (pinfunction "2_2") (pintype "passive"))
      (node (ref "T4") (pin "3") (pinfunction "C_3") (pintype "passive"))
    )
    (net (code "77") (name "Net-(T5-B)") (class "Default")
      (node (ref "R5") (pin "2") (pinfunction "2_2") (pintype "passive"))
      (node (ref "T5") (pin "1") (pinfunction "B_1") (pintype "passive"))
    )
    (net (code "78") (name "Net-(T5-C)") (class "Default")
      (node (ref "D5") (pin "A") (pinfunction "A_A") (pintype "passive"))
      (node (ref "K5") (pin "2") (pinfunction "2_2") (pintype "passive"))
      (node (ref "T5") (pin "3") (pinfunction "C_3") (pintype "passive"))
    )
    (net (code "79") (name "Net-(T6-B)") (class "Default")
      (node (ref "R6") (pin "2") (pinfunction "2_2") (pintype "passive"))
      (node (ref "T6") (pin "1") (pinfunction "B_1") (pintype "passive"))
    )
    (net (code "80") (name "Net-(T6-C)") (class "Default")
      (node (ref "D6") (pin "A") (pinfunction "A_A") (pintype "passive"))
      (node (ref "K6") (pin "2") (pinfunction "2_2") (pintype "passive"))
      (node (ref "T6") (pin "3") (pinfunction "C_3") (pintype "passive"))
    )
    (net (code "81") (name "Net-(T7-B)") (class "Default")
      (node (ref "R7") (pin "2") (pinfunction "2_2") (pintype "passive"))
      (node (ref "T7") (pin "1") (pinfunction "B_1") (pintype "passive"))
    )
    (net (code "82") (name "Net-(T7-C)") (class "Default")
      (node (ref "D7") (pin "A") (pinfunction "A_A") (pintype "passive"))
      (node (ref "K7") (pin "2") (pinfunction "2_2") (pintype "passive"))
      (node (ref "T7") (pin "3") (pinfunction "C_3") (pintype "passive"))
    )
    (net (code "83") (name "Net-(T8-B)") (class "Default")
      (node (ref "R8") (pin "2") (pinfunction "2_2") (pintype "passive"))
      (node (ref "T8") (pin "1") (pinfunction "B_1") (pintype "passive"))
    )
    (net (code "84") (name "Net-(T8-C)") (class "Default")
      (node (ref "D8") (pin "A") (pinfunction "A_A") (pintype "passive"))
      (node (ref "K8") (pin "2") (pinfunction "2_2") (pintype "passive"))
      (node (ref "T8") (pin "3") (pinfunction "C_3") (pintype "passive"))
    )
    (net (code "85") (name "Net-(T9-B)") (class "Default")
      (node (ref "R9") (pin "2") (pinfunction "2_2") (pintype "passive"))
      (node (ref "T9") (pin "1") (pinfunction "B_1") (pintype "passive"))
    )
    (net (code "86") (name "Net-(T9-C)") (class "Default")
      (node (ref "D9") (pin "A") (pinfunction "A_A") (pintype "passive"))
      (node (ref "K9") (pin "2") (pinfunction "2_2") (pintype "passive"))
      (node (ref "T9") (pin "3") (pinfunction "C_3") (pintype "passive"))
    )
    (net (code "87") (name "Net-(T10-B)") (class "Default")
      (node (ref "R10") (pin "2") (pinfunction "2_2") (pintype "passive"))
      (node (ref "T10") (pin "1") (pinfunction "B_1") (pintype "passive"))
    )
    (net (code "88") (name "Net-(T10-C)") (class "Default")
      (node (ref "D11") (pin "A") (pinfunction "A_A") (pintype "passive"))
      (node (ref "K10") (pin "2") (pinfunction "2_2") (pintype "passive"))
      (node (ref "T10") (pin "3") (pinfunction "C_3") (pintype "passive"))
    )
    (net (code "89") (name "Net-(T11-B)") (class "Default")
      (node (ref "R13") (pin "2") (pinfunction "2_2") (pintype "passive"))
      (node (ref "T11") (pin "1") (pinfunction "B_1") (pintype "passive"))
    )
    (net (code "90") (name "Net-(T11-C)") (class "Default")
      (node (ref "D12") (pin "A") (pinfunction "A_A") (pintype "passive"))
      (node (ref "K11") (pin "2") (pinfunction "2_2") (pintype "passive"))
      (node (ref "T11") (pin "3") (pinfunction "C_3") (pintype "passive"))
    )
    (net (code "91") (name "Net-(T12-B)") (class "Default")
      (node (ref "R14") (pin "2") (pinfunction "2_2") (pintype "passive"))
      (node (ref "T12") (pin "1") (pinfunction "B_1") (pintype "passive"))
    )
    (net (code "92") (name "Net-(T12-C)") (class "Default")
      (node (ref "D13") (pin "A") (pinfunction "A_A") (pintype "passive"))
      (node (ref "K12") (pin "2") (pinfunction "2_2") (pintype "passive"))
      (node (ref "T12") (pin "3") (pinfunction "C_3") (pintype "passive"))
    )
    (net (code "93") (name "unconnected-(IC3-(PCINT0{slash}ADC0)PA0-Pad37)") (class "Default")
      (node (ref "IC3") (pin "37") (pinfunction "(PCINT0/ADC0)PA0_37") (pintype "bidirectional"))
    )
    (net (code "94") (name "unconnected-(IC3-(PCINT1{slash}ADC1)PA1-Pad36)") (class "Default")
      (node (ref "IC3") (pin "36") (pinfunction "(PCINT1/ADC1)PA1_36") (pintype "bidirectional"))
    )
    (net (code "95") (name "unconnected-(IC3-(PCINT2{slash}ADC2)PA2-Pad35)") (class "Default")
      (node (ref "IC3") (pin "35") (pinfunction "(PCINT2/ADC2)PA2_35") (pintype "bidirectional"))
    )
    (net (code "96") (name "unconnected-(IC3-(PCINT3{slash}ADC3)PA3-Pad34)") (class "Default")
      (node (ref "IC3") (pin "34") (pinfunction "(PCINT3/ADC3)PA3_34") (pintype "bidirectional"))
    )
    (net (code "97") (name "unconnected-(IC3-(PCINT5{slash}ADC5)PA5-Pad32)") (class "Default")
      (node (ref "IC3") (pin "32") (pinfunction "(PCINT5/ADC5)PA5_32") (pintype "bidirectional"))
    )
    (net (code "98") (name "unconnected-(IC3-(PCINT8{slash}XCK0{slash}T0)PB0-Pad40)") (class "Default")
      (node (ref "IC3") (pin "40") (pinfunction "(PCINT8/XCK0/T0)PB0_40") (pintype "bidirectional"))
    )
    (net (code "99") (name "unconnected-(IC3-(PCINT9{slash}CLKO{slash}T1)PB1-Pad41)") (class "Default")
      (node (ref "IC3") (pin "41") (pinfunction "(PCINT9/CLKO/T1)PB1_41") (pintype "bidirectional"))
    )
    (net (code "100") (name "unconnected-(IC3-(PCINT10{slash}INT2{slash}AIN0)PB2-Pad42)") (class "Default")
      (node (ref "IC3") (pin "42") (pinfunction "(PCINT10/INT2/AIN0)PB2_42") (pintype "bidirectional"))
    )
    (net (code "101") (name "unconnected-(IC3-(PCINT11{slash}OC0A{slash}AIN1)PB3-Pad43)") (class "Default")
      (node (ref "IC3") (pin "43") (pinfunction "(PCINT11/OC0A/AIN1)PB3_43") (pintype "bidirectional"))
    )
    (net (code "102") (name "unconnected-(IC3-(PCINT17{slash}SDA)PC1-Pad20)") (class "Default")
      (node (ref "IC3") (pin "20") (pinfunction "(PCINT17/SDA)PC1_20") (pintype "output"))
    )
    (net (code "103") (name "unconnected-(IC3-(PCINT18{slash}TCK)PC2-Pad21)") (class "Default")
      (node (ref "IC3") (pin "21") (pinfunction "(PCINT18/TCK)PC2_21") (pintype "output"))
    )
    (net (code "104") (name "unconnected-(IC3-(PCINT19{slash}TMS)PC3-Pad22)") (class "Default")
      (node (ref "IC3") (pin "22") (pinfunction "(PCINT19/TMS)PC3_22") (pintype "output"))
    )
    (net (code "105") (name "unconnected-(IC3-(PCINT24{slash}RXD0)PD0-Pad9)") (class "Default")
      (node (ref "IC3") (pin "9") (pinfunction "(PCINT24/RXD0)PD0_9") (pintype "bidirectional"))
    )
    (net (code "106") (name "unconnected-(IC3-(PCINT25{slash}TXD0)PD1-Pad10)") (class "Default")
      (node (ref "IC3") (pin "10") (pinfunction "(PCINT25/TXD0)PD1_10") (pintype "bidirectional"))
    )
    (net (code "107") (name "unconnected-(IC3-(PCINT26{slash}INT0)PD2-Pad11)") (class "Default")
      (node (ref "IC3") (pin "11") (pinfunction "(PCINT26/INT0)PD2_11") (pintype "bidirectional"))
    )
    (net (code "108") (name "unconnected-(IC3-AREF-Pad29)") (class "Default")
      (node (ref "IC3") (pin "29") (pinfunction "AREF_29") (pintype "passive"))
    )
    (net (code "109") (name "unconnected-(X9-Pad7)") (class "Default")
      (node (ref "X9") (pin "7") (pinfunction "7_7") (pintype "passive"))
    )
  )
)
